# bluetooth.net
KiCad netlist of a schematic drawn in EAGLE
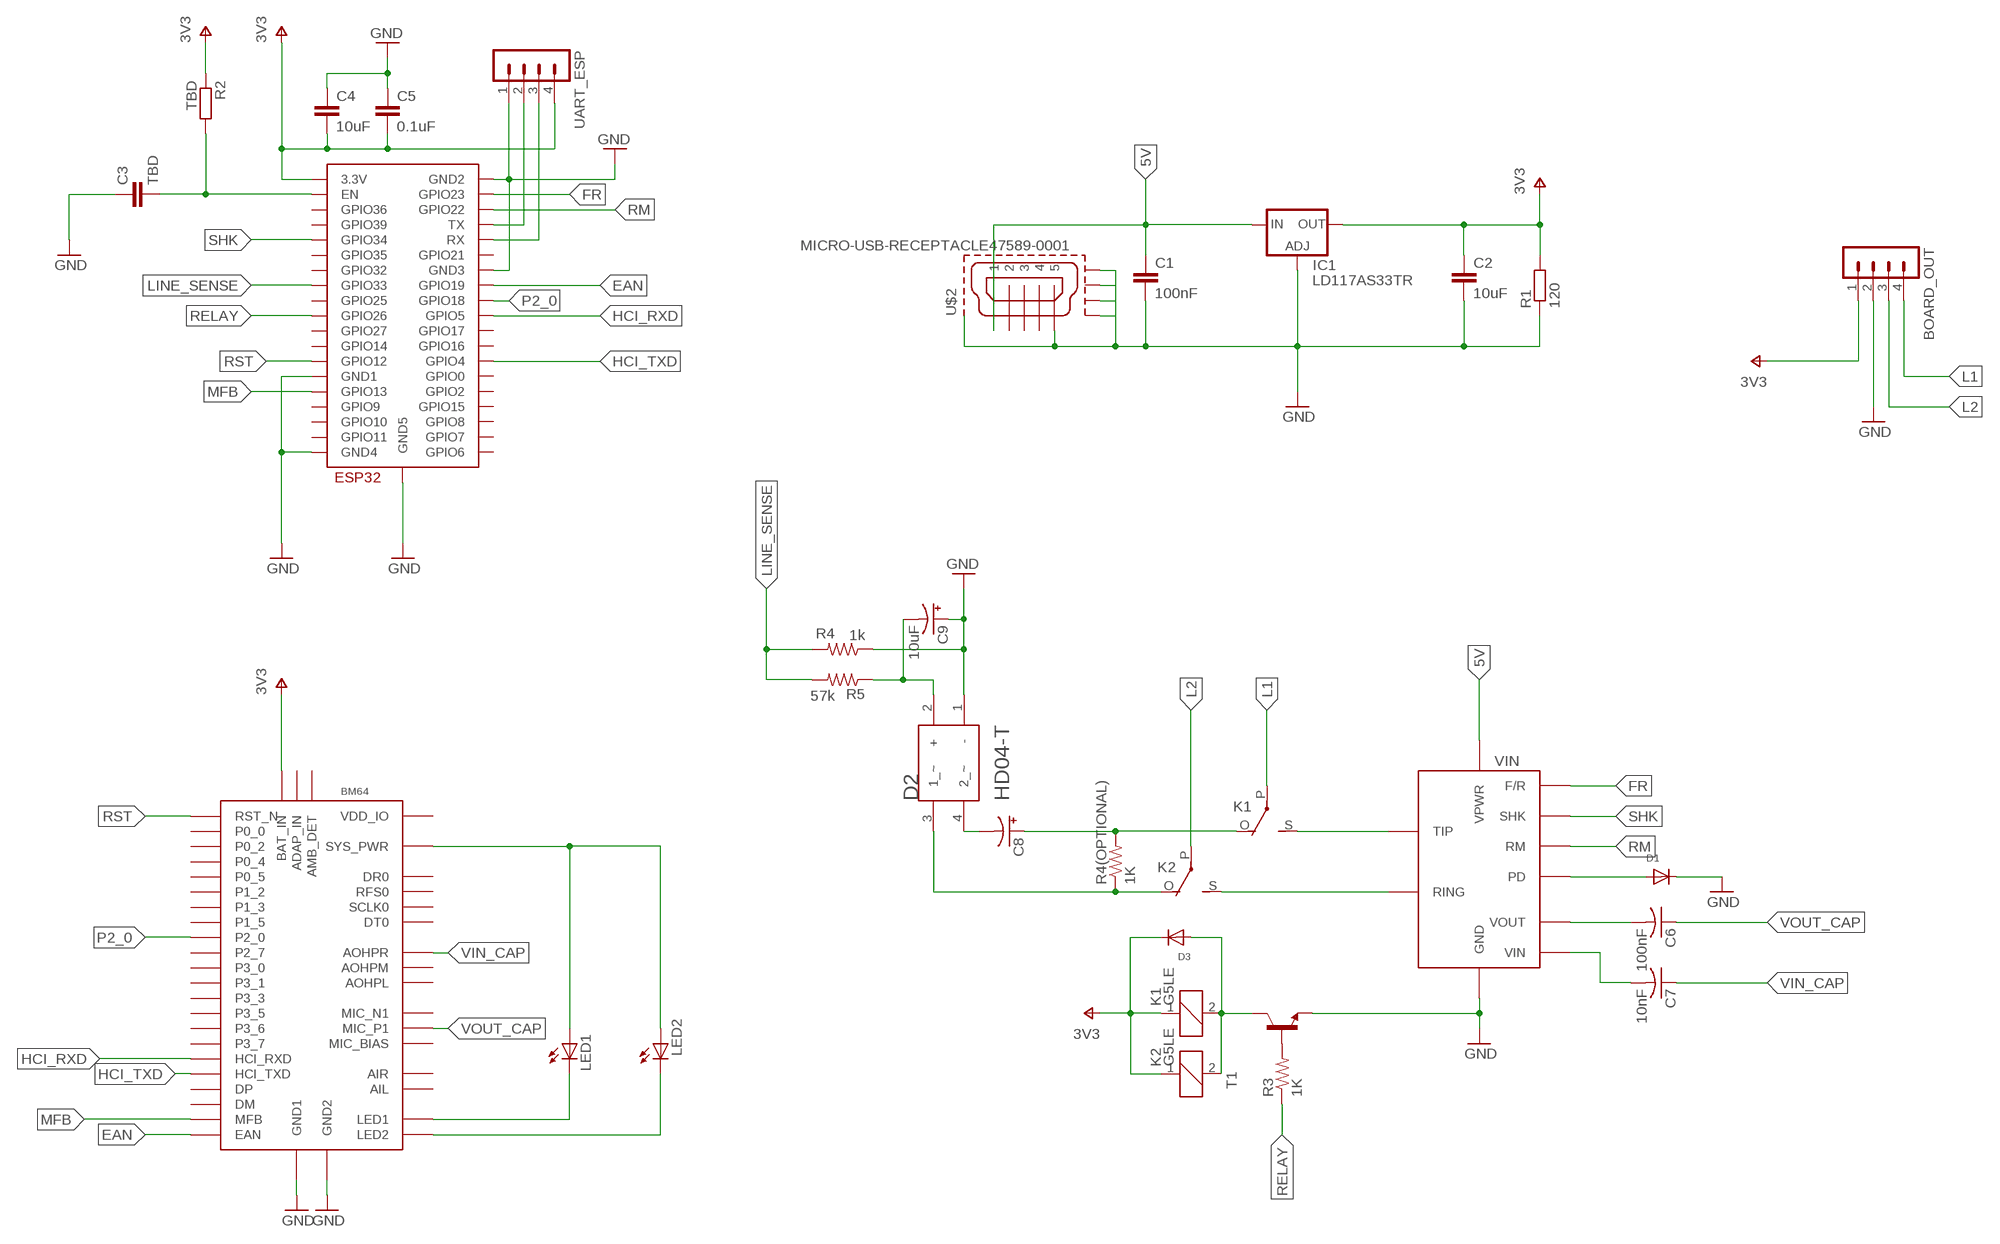
[diagram p0: schematic, sheet 1]

(export (version "E")
  (design (tool "Eeschema 10.0.6"))
  (components
    (comp (ref "BM64")
      (value "DJD_EAGLE_LIBRARY_BM64")
      (footprint "eagle-import:DJD_EAGLE_LIBRARY_BM64")
      (libsource (lib "eagle-import") (part "DJD_EAGLE_LIBRARY_BM64"))
    )
    (comp (ref "BOARD_OUT")
      (value "MA04-1")
      (footprint "eagle-import:MA04-1")
      (libsource (lib "eagle-import") (part "MA04-1"))
    )
    (comp (ref "C1")
      (value "100nF")
      (footprint "eagle-import:C0805")
      (libsource (lib "eagle-import") (part "C-EUC0805"))
    )
    (comp (ref "C2")
      (value "10uF")
      (footprint "eagle-import:C0805")
      (libsource (lib "eagle-import") (part "C-EUC0805"))
    )
    (comp (ref "C3")
      (value "TBD")
      (footprint "eagle-import:C0805")
      (libsource (lib "eagle-import") (part "C-EUC0805"))
    )
    (comp (ref "C4")
      (value "10uF")
      (footprint "eagle-import:C0805")
      (libsource (lib "eagle-import") (part "C-EUC0805"))
    )
    (comp (ref "C5")
      (value "0.1uF")
      (footprint "eagle-import:C0805")
      (libsource (lib "eagle-import") (part "C-EUC0805"))
    )
    (comp (ref "C6")
      (value "100nF")
      (footprint "eagle-import:C0805")
      (libsource (lib "eagle-import") (part "C-USC0805"))
    )
    (comp (ref "C7")
      (value "10nF")
      (footprint "eagle-import:C0805")
      (libsource (lib "eagle-import") (part "C-USC0805"))
    )
    (comp (ref "C8")
      (value "CPOL-USE2-5")
      (footprint "eagle-import:E2-5")
      (libsource (lib "eagle-import") (part "CPOL-USE2-5"))
    )
    (comp (ref "C9")
      (value "10uF")
      (footprint "eagle-import:CPOL-RADIAL-2.5MM-5MM")
      (libsource (lib "eagle-import") (part "10UF-POLAR-RADIAL-2.5MM-25V-20%"))
    )
    (comp (ref "D1")
      (value "DIODESMA")
      (footprint "eagle-import:SMADIODE")
      (libsource (lib "eagle-import") (part "DIODESMA"))
    )
    (comp (ref "D2")
      (value "DIODES_HD04-TDIODES_HD04-T_0_0")
      (footprint "eagle-import:DIODES_HD04-T_0")
      (fields
        (field (name "DIGIKEY_PART_NUMBER") "HD04DICT-ND")
        (field (name "MF") "Diodes")
        (field (name "MOUSER_PART_NUMBER") "621-HD04T")
      )
      (libsource (lib "eagle-import") (part "DIODES_HD04-TDIODES_HD04-T_0_0"))
    )
    (comp (ref "D3")
      (value "DIODESOD-123")
      (footprint "eagle-import:SOD-123")
      (libsource (lib "eagle-import") (part "DIODESOD-123"))
    )
    (comp (ref "IC1")
      (value "LD117AS33TR")
      (footprint "eagle-import:SOT223")
      (libsource (lib "eagle-import") (part "LD117A?S33TR"))
    )
    (comp (ref "K1")
      (value "G5LE")
      (footprint "eagle-import:G5LE")
      (libsource (lib "eagle-import") (part "G5LE"))
    )
    (comp (ref "K2")
      (value "G5LE")
      (footprint "eagle-import:G5LE")
      (libsource (lib "eagle-import") (part "G5LE"))
    )
    (comp (ref "LED1")
      (value "LEDCHIP-LED0805")
      (footprint "eagle-import:CHIP-LED0805")
      (libsource (lib "eagle-import") (part "LEDCHIP-LED0805"))
    )
    (comp (ref "LED2")
      (value "LEDCHIP-LED0805")
      (footprint "eagle-import:CHIP-LED0805")
      (libsource (lib "eagle-import") (part "LEDCHIP-LED0805"))
    )
    (comp (ref "R1")
      (value "120")
      (footprint "eagle-import:M0805")
      (libsource (lib "eagle-import") (part "R-EU_M0805"))
    )
    (comp (ref "R2")
      (value "TBD")
      (footprint "eagle-import:M0805")
      (libsource (lib "eagle-import") (part "R-EU_M0805"))
    )
    (comp (ref "R3")
      (value "1K")
      (footprint "eagle-import:M0805")
      (libsource (lib "eagle-import") (part "R-US_M0805"))
    )
    (comp (ref "R4")
      (value "1k")
      (footprint "eagle-import:M0805")
      (libsource (lib "eagle-import") (part "R-US_M0805"))
    )
    (comp (ref "R4(OPTIONAL)")
      (value "1K")
      (footprint "eagle-import:M0805")
      (libsource (lib "eagle-import") (part "R-US_M0805"))
    )
    (comp (ref "R5")
      (value "57k")
      (footprint "eagle-import:M0805")
      (libsource (lib "eagle-import") (part "R-US_M0805"))
    )
    (comp (ref "T1")
      (value "-NPN-SOT23-EBC")
      (footprint "eagle-import:SOT23-EBC")
      (libsource (lib "eagle-import") (part "-NPN-SOT23-EBC"))
    )
    (comp (ref "U$1")
      (value "ESP32-WROOM")
      (footprint "eagle-import:ESP32-WROOM")
      (libsource (lib "eagle-import") (part "ESP32-WROOM"))
    )
    (comp (ref "U$2")
      (value "MICRO-USB-RECEPTACLE47589-0001")
      (footprint "eagle-import:47589-0001")
      (libsource (lib "eagle-import") (part "MICRO-USB-RECEPTACLE47589-0001"))
    )
    (comp (ref "UART_ESP")
      (value "MA04-1")
      (footprint "eagle-import:MA04-1")
      (libsource (lib "eagle-import") (part "MA04-1"))
    )
    (comp (ref "VIN")
      (value "DJD_EAGLE_LIBRARY_AG1171SIL")
      (footprint "eagle-import:DJD_EAGLE_LIBRARY_AG1171")
      (libsource (lib "eagle-import") (part "DJD_EAGLE_LIBRARY_AG1171SIL"))
    )
  )
  (nets
    (net (code "1") (name "/ADAP_IN") (class "Default")
      (node (ref "BM64") (pin "23") (pinfunction "ADAP_IN_23") (pintype "power_in"))
    )
    (net (code "2") (name "/MIC_BIAS") (class "Default")
      (node (ref "BM64") (pin "10") (pinfunction "MIC_BIAS_10") (pintype "power_in"))
    )
    (net (code "3") (name "/VDD_IO") (class "Default")
      (node (ref "BM64") (pin "21") (pinfunction "VDD_IO_21") (pintype "power_in"))
    )
    (net (code "4") (name "3V3") (class "Default")
      (node (ref "BM64") (pin "22") (pinfunction "BAT_IN_22") (pintype "power_in"))
      (node (ref "BOARD_OUT") (pin "1") (pinfunction "1_1") (pintype "passive"))
      (node (ref "C2") (pin "1") (pinfunction "1_1") (pintype "passive"))
      (node (ref "C4") (pin "2") (pinfunction "2_2") (pintype "passive"))
      (node (ref "C5") (pin "2") (pinfunction "2_2") (pintype "passive"))
      (node (ref "D3") (pin "C") (pinfunction "C_C") (pintype "passive"))
      (node (ref "IC1") (pin "4") (pinfunction "OUT_4") (pintype "passive"))
      (node (ref "K1") (pin "1") (pinfunction "1_1") (pintype "passive"))
      (node (ref "K2") (pin "1") (pinfunction "1_1") (pintype "passive"))
      (node (ref "R1") (pin "2") (pinfunction "2_2") (pintype "passive"))
      (node (ref "R2") (pin "1") (pinfunction "1_1") (pintype "passive"))
      (node (ref "U$1") (pin "3V3") (pinfunction "3.3V_3V3") (pintype "bidirectional"))
      (node (ref "UART_ESP") (pin "4") (pinfunction "4_4") (pintype "passive"))
    )
    (net (code "5") (name "5V") (class "Default")
      (node (ref "C1") (pin "1") (pinfunction "1_1") (pintype "passive"))
      (node (ref "IC1") (pin "3") (pinfunction "IN_3") (pintype "input"))
      (node (ref "U$2") (pin "1") (pinfunction "1_1") (pintype "input"))
      (node (ref "VIN") (pin "P$13") (pinfunction "VPWR_P$13") (pintype "power_in"))
    )
    (net (code "6") (name "EAN") (class "Default")
      (node (ref "BM64") (pin "32") (pinfunction "EAN_32") (pintype "input"))
      (node (ref "U$1") (pin "IO19") (pinfunction "GPIO19_IO19") (pintype "bidirectional"))
    )
    (net (code "7") (name "FR") (class "Default")
      (node (ref "U$1") (pin "IO23") (pinfunction "GPIO23_IO23") (pintype "bidirectional"))
      (node (ref "VIN") (pin "P$3") (pinfunction "F/R_P$3") (pintype "input"))
    )
    (net (code "8") (name "GND") (class "Default")
      (node (ref "BM64") (pin "14") (pinfunction "GND1_14") (pintype "power_in"))
      (node (ref "BM64") (pin "43") (pinfunction "GND2_43") (pintype "power_in"))
      (node (ref "BOARD_OUT") (pin "2") (pinfunction "2_2") (pintype "passive"))
      (node (ref "C1") (pin "2") (pinfunction "2_2") (pintype "passive"))
      (node (ref "C2") (pin "2") (pinfunction "2_2") (pintype "passive"))
      (node (ref "C3") (pin "1") (pinfunction "1_1") (pintype "passive"))
      (node (ref "C4") (pin "1") (pinfunction "1_1") (pintype "passive"))
      (node (ref "C5") (pin "1") (pinfunction "1_1") (pintype "passive"))
      (node (ref "C9") (pin "1") (pinfunction "+_1") (pintype "passive"))
      (node (ref "D1") (pin "C") (pinfunction "C_C") (pintype "passive"))
      (node (ref "D2") (pin "1") (pinfunction "-_1") (pintype "passive"))
      (node (ref "IC1") (pin "1") (pinfunction "ADJ_1") (pintype "input"))
      (node (ref "R1") (pin "1") (pinfunction "1_1") (pintype "passive"))
      (node (ref "R4") (pin "1") (pinfunction "1_1") (pintype "passive"))
      (node (ref "T1") (pin "E") (pinfunction "E_E") (pintype "passive"))
      (node (ref "U$1") (pin "GND1") (pinfunction "GND1_GND1") (pintype "bidirectional"))
      (node (ref "U$1") (pin "GND2") (pinfunction "GND2_GND2") (pintype "bidirectional"))
      (node (ref "U$1") (pin "GND3") (pinfunction "GND3_GND3") (pintype "bidirectional"))
      (node (ref "U$1") (pin "GND4") (pinfunction "GND4_GND4") (pintype "bidirectional"))
      (node (ref "U$1") (pin "GND5") (pinfunction "GND5_GND5") (pintype "bidirectional"))
      (node (ref "U$2") (pin "5") (pinfunction "5_5") (pintype "input"))
      (node (ref "U$2") (pin "CASING1") (pinfunction "GND1_CASING1") (pintype "bidirectional"))
      (node (ref "U$2") (pin "CASING2") (pinfunction "GND2_CASING2") (pintype "bidirectional"))
      (node (ref "U$2") (pin "CASING3") (pinfunction "GND3_CASING3") (pintype "bidirectional"))
      (node (ref "U$2") (pin "CASING4") (pinfunction "GND4_CASING4") (pintype "bidirectional"))
      (node (ref "UART_ESP") (pin "1") (pinfunction "1_1") (pintype "passive"))
      (node (ref "VIN") (pin "P$12") (pinfunction "GND_P$12") (pintype "power_in"))
    )
    (net (code "9") (name "HCI_RXD") (class "Default")
      (node (ref "BM64") (pin "19") (pinfunction "HCI_RXD_19") (pintype "input"))
      (node (ref "U$1") (pin "IO5") (pinfunction "GPIO5_IO5") (pintype "bidirectional"))
    )
    (net (code "10") (name "HCI_TXD") (class "Default")
      (node (ref "BM64") (pin "20") (pinfunction "HCI_TXD_20") (pintype "output"))
      (node (ref "U$1") (pin "IO4") (pinfunction "GPIO4_IO4") (pintype "bidirectional"))
    )
    (net (code "11") (name "L1") (class "Default")
      (node (ref "BOARD_OUT") (pin "4") (pinfunction "4_4") (pintype "passive"))
      (node (ref "K1") (pin "P") (pinfunction "P_P") (pintype "passive"))
    )
    (net (code "12") (name "L2") (class "Default")
      (node (ref "BOARD_OUT") (pin "3") (pinfunction "3_3") (pintype "passive"))
      (node (ref "K2") (pin "P") (pinfunction "P_P") (pintype "passive"))
    )
    (net (code "13") (name "LINE_SENSE") (class "Default")
      (node (ref "R4") (pin "2") (pinfunction "2_2") (pintype "passive"))
      (node (ref "R5") (pin "2") (pinfunction "2_2") (pintype "passive"))
      (node (ref "U$1") (pin "IO33") (pinfunction "GPIO33_IO33") (pintype "bidirectional"))
    )
    (net (code "14") (name "MFB") (class "Default")
      (node (ref "BM64") (pin "26") (pinfunction "MFB_26") (pintype "input"))
      (node (ref "U$1") (pin "IO13") (pinfunction "GPIO13_IO13") (pintype "bidirectional"))
    )
    (net (code "15") (name "Net-(BM64-LED1)") (class "Default")
      (node (ref "BM64") (pin "28") (pinfunction "LED1_28") (pintype "output"))
      (node (ref "LED1") (pin "C") (pinfunction "C_C") (pintype "passive"))
    )
    (net (code "16") (name "Net-(BM64-LED2)") (class "Default")
      (node (ref "BM64") (pin "27") (pinfunction "LED2_27") (pintype "output"))
      (node (ref "LED2") (pin "C") (pinfunction "C_C") (pintype "passive"))
    )
    (net (code "17") (name "Net-(BM64-SYS_PWR)") (class "Default")
      (node (ref "BM64") (pin "24") (pinfunction "SYS_PWR_24") (pintype "power_in"))
      (node (ref "LED1") (pin "A") (pinfunction "A_A") (pintype "passive"))
      (node (ref "LED2") (pin "A") (pinfunction "A_A") (pintype "passive"))
    )
    (net (code "18") (name "Net-(C3-Pad2)") (class "Default")
      (node (ref "C3") (pin "2") (pinfunction "2_2") (pintype "passive"))
      (node (ref "R2") (pin "2") (pinfunction "2_2") (pintype "passive"))
      (node (ref "U$1") (pin "EN") (pinfunction "EN_EN") (pintype "bidirectional"))
    )
    (net (code "19") (name "Net-(C8-Pad+)") (class "Default")
      (node (ref "C8") (pin "+") (pinfunction "+_+") (pintype "passive"))
      (node (ref "K1") (pin "O") (pinfunction "O_O") (pintype "passive"))
      (node (ref "R4(OPTIONAL)") (pin "2") (pinfunction "2_2") (pintype "passive"))
    )
    (net (code "20") (name "Net-(C9--)") (class "Default")
      (node (ref "C9") (pin "2") (pinfunction "-_2") (pintype "passive"))
      (node (ref "D2") (pin "2") (pinfunction "+_2") (pintype "passive"))
      (node (ref "R5") (pin "1") (pinfunction "1_1") (pintype "passive"))
    )
    (net (code "21") (name "Net-(D2-1_~{})") (class "Default")
      (node (ref "D2") (pin "3") (pinfunction "1_~{}_3") (pintype "passive"))
      (node (ref "K2") (pin "O") (pinfunction "O_O") (pintype "passive"))
      (node (ref "R4(OPTIONAL)") (pin "1") (pinfunction "1_1") (pintype "passive"))
    )
    (net (code "22") (name "Net-(D2-2_~{})") (class "Default")
      (node (ref "C8") (pin "-") (pinfunction "-_-") (pintype "passive"))
      (node (ref "D2") (pin "4") (pinfunction "2_~{}_4") (pintype "passive"))
    )
    (net (code "23") (name "Net-(D3-PadA)") (class "Default")
      (node (ref "D3") (pin "A") (pinfunction "A_A") (pintype "passive"))
      (node (ref "K1") (pin "2") (pinfunction "2_2") (pintype "passive"))
      (node (ref "K2") (pin "2") (pinfunction "2_2") (pintype "passive"))
      (node (ref "T1") (pin "C") (pinfunction "C_C") (pintype "passive"))
    )
    (net (code "24") (name "Net-(R3-Pad2)") (class "Default")
      (node (ref "R3") (pin "2") (pinfunction "2_2") (pintype "passive"))
      (node (ref "T1") (pin "B") (pinfunction "B_B") (pintype "passive"))
    )
    (net (code "25") (name "Net-(U$1-PadRX)") (class "Default")
      (node (ref "U$1") (pin "RX") (pinfunction "RX_RX") (pintype "bidirectional"))
      (node (ref "UART_ESP") (pin "3") (pinfunction "3_3") (pintype "passive"))
    )
    (net (code "26") (name "Net-(U$1-PadTX)") (class "Default")
      (node (ref "U$1") (pin "TX") (pinfunction "TX_TX") (pintype "bidirectional"))
      (node (ref "UART_ESP") (pin "2") (pinfunction "2_2") (pintype "passive"))
    )
    (net (code "27") (name "Net-(VIN-PD)") (class "Default")
      (node (ref "D1") (pin "A") (pinfunction "A_A") (pintype "passive"))
      (node (ref "VIN") (pin "P$14") (pinfunction "PD_P$14") (pintype "input"))
    )
    (net (code "28") (name "Net-(VIN-RING)") (class "Default")
      (node (ref "K2") (pin "S") (pinfunction "S_S") (pintype "passive"))
      (node (ref "VIN") (pin "P$1") (pinfunction "RING_P$1") (pintype "bidirectional"))
    )
    (net (code "29") (name "Net-(VIN-TIP)") (class "Default")
      (node (ref "K1") (pin "S") (pinfunction "S_S") (pintype "passive"))
      (node (ref "VIN") (pin "P$2") (pinfunction "TIP_P$2") (pintype "bidirectional"))
    )
    (net (code "30") (name "Net-(VIN-VIN)") (class "Default")
      (node (ref "C7") (pin "2") (pinfunction "2_2") (pintype "passive"))
      (node (ref "VIN") (pin "P$9") (pinfunction "VIN_P$9") (pintype "input"))
    )
    (net (code "31") (name "Net-(VIN-VOUT)") (class "Default")
      (node (ref "C6") (pin "2") (pinfunction "2_2") (pintype "passive"))
      (node (ref "VIN") (pin "P$10") (pinfunction "VOUT_P$10") (pintype "output"))
    )
    (net (code "32") (name "P2_0") (class "Default")
      (node (ref "BM64") (pin "41") (pinfunction "P2_0_41") (pintype "bidirectional"))
      (node (ref "U$1") (pin "IO18") (pinfunction "GPIO18_IO18") (pintype "bidirectional"))
    )
    (net (code "33") (name "RELAY") (class "Default")
      (node (ref "R3") (pin "1") (pinfunction "1_1") (pintype "passive"))
      (node (ref "U$1") (pin "IO26") (pinfunction "GPIO26_IO26") (pintype "bidirectional"))
    )
    (net (code "34") (name "RM") (class "Default")
      (node (ref "U$1") (pin "IO22") (pinfunction "GPIO22_IO22") (pintype "bidirectional"))
      (node (ref "VIN") (pin "P$4") (pinfunction "RM_P$4") (pintype "input"))
    )
    (net (code "35") (name "RST") (class "Default")
      (node (ref "BM64") (pin "13") (pinfunction "RST_N_13") (pintype "input"))
      (node (ref "U$1") (pin "IO12") (pinfunction "GPIO12_IO12") (pintype "bidirectional"))
    )
    (net (code "36") (name "SHK") (class "Default")
      (node (ref "U$1") (pin "IO34") (pinfunction "GPIO34_IO34") (pintype "bidirectional"))
      (node (ref "VIN") (pin "P$5") (pinfunction "SHK_P$5") (pintype "output"))
    )
    (net (code "37") (name "VIN_CAP") (class "Default")
      (node (ref "BM64") (pin "5") (pinfunction "AOHPR_5") (pintype "passive"))
      (node (ref "C7") (pin "1") (pinfunction "1_1") (pintype "passive"))
    )
    (net (code "38") (name "VOUT_CAP") (class "Default")
      (node (ref "BM64") (pin "9") (pinfunction "MIC_P1_9") (pintype "passive"))
      (node (ref "C6") (pin "1") (pinfunction "1_1") (pintype "passive"))
    )
    (net (code "39") (name "unconnected-(BM64-AIL-Pad12)") (class "Default")
      (node (ref "BM64") (pin "12") (pinfunction "AIL_12") (pintype "passive"))
    )
    (net (code "40") (name "unconnected-(BM64-AIR-Pad11)") (class "Default")
      (node (ref "BM64") (pin "11") (pinfunction "AIR_11") (pintype "passive"))
    )
    (net (code "41") (name "unconnected-(BM64-AMB_DET-Pad25)") (class "Default")
      (node (ref "BM64") (pin "25") (pinfunction "AMB_DET_25") (pintype "passive"))
    )
    (net (code "42") (name "unconnected-(BM64-AOHPL-Pad7)") (class "Default")
      (node (ref "BM64") (pin "7") (pinfunction "AOHPL_7") (pintype "passive"))
    )
    (net (code "43") (name "unconnected-(BM64-AOHPM-Pad6)") (class "Default")
      (node (ref "BM64") (pin "6") (pinfunction "AOHPM_6") (pintype "passive"))
    )
    (net (code "44") (name "unconnected-(BM64-DM-Pad33)") (class "Default")
      (node (ref "BM64") (pin "33") (pinfunction "DM_33") (pintype "bidirectional"))
    )
    (net (code "45") (name "unconnected-(BM64-DP-Pad34)") (class "Default")
      (node (ref "BM64") (pin "34") (pinfunction "DP_34") (pintype "bidirectional"))
    )
    (net (code "46") (name "unconnected-(BM64-DR0-Pad1)") (class "Default")
      (node (ref "BM64") (pin "1") (pinfunction "DR0_1") (pintype "bidirectional"))
    )
    (net (code "47") (name "unconnected-(BM64-DT0-Pad4)") (class "Default")
      (node (ref "BM64") (pin "4") (pinfunction "DT0_4") (pintype "bidirectional"))
    )
    (net (code "48") (name "unconnected-(BM64-MIC_N1-Pad8)") (class "Default")
      (node (ref "BM64") (pin "8") (pinfunction "MIC_N1_8") (pintype "passive"))
    )
    (net (code "49") (name "unconnected-(BM64-P0_0-Pad31)") (class "Default")
      (node (ref "BM64") (pin "31") (pinfunction "P0_0_31") (pintype "bidirectional"))
    )
    (net (code "50") (name "unconnected-(BM64-P0_2-Pad40)") (class "Default")
      (node (ref "BM64") (pin "40") (pinfunction "P0_2_40") (pintype "bidirectional"))
    )
    (net (code "51") (name "unconnected-(BM64-P0_4-Pad17)") (class "Default")
      (node (ref "BM64") (pin "17") (pinfunction "P0_4_17") (pintype "bidirectional"))
    )
    (net (code "52") (name "unconnected-(BM64-P0_5-Pad35)") (class "Default")
      (node (ref "BM64") (pin "35") (pinfunction "P0_5_35") (pintype "bidirectional"))
    )
    (net (code "53") (name "unconnected-(BM64-P1_2-Pad15)") (class "Default")
      (node (ref "BM64") (pin "15") (pinfunction "P1_2_15") (pintype "bidirectional"))
    )
    (net (code "54") (name "unconnected-(BM64-P1_3-Pad16)") (class "Default")
      (node (ref "BM64") (pin "16") (pinfunction "P1_3_16") (pintype "bidirectional"))
    )
    (net (code "55") (name "unconnected-(BM64-P1_5-Pad18)") (class "Default")
      (node (ref "BM64") (pin "18") (pinfunction "P1_5_18") (pintype "bidirectional"))
    )
    (net (code "56") (name "unconnected-(BM64-P2_7-Pad42)") (class "Default")
      (node (ref "BM64") (pin "42") (pinfunction "P2_7_42") (pintype "bidirectional"))
    )
    (net (code "57") (name "unconnected-(BM64-P3_0-Pad36)") (class "Default")
      (node (ref "BM64") (pin "36") (pinfunction "P3_0_36") (pintype "bidirectional"))
    )
    (net (code "58") (name "unconnected-(BM64-P3_1-Pad37)") (class "Default")
      (node (ref "BM64") (pin "37") (pinfunction "P3_1_37") (pintype "bidirectional"))
    )
    (net (code "59") (name "unconnected-(BM64-P3_3-Pad38)") (class "Default")
      (node (ref "BM64") (pin "38") (pinfunction "P3_3_38") (pintype "bidirectional"))
    )
    (net (code "60") (name "unconnected-(BM64-P3_5-Pad30)") (class "Default")
      (node (ref "BM64") (pin "30") (pinfunction "P3_5_30") (pintype "bidirectional"))
    )
    (net (code "61") (name "unconnected-(BM64-P3_6-Pad39)") (class "Default")
      (node (ref "BM64") (pin "39") (pinfunction "P3_6_39") (pintype "bidirectional"))
    )
    (net (code "62") (name "unconnected-(BM64-P3_7-Pad29)") (class "Default")
      (node (ref "BM64") (pin "29") (pinfunction "P3_7_29") (pintype "bidirectional"))
    )
    (net (code "63") (name "unconnected-(BM64-RFS0-Pad2)") (class "Default")
      (node (ref "BM64") (pin "2") (pinfunction "RFS0_2") (pintype "bidirectional"))
    )
    (net (code "64") (name "unconnected-(BM64-SCLK0-Pad3)") (class "Default")
      (node (ref "BM64") (pin "3") (pinfunction "SCLK0_3") (pintype "bidirectional"))
    )
    (net (code "65") (name "unconnected-(U$1-GPIO0-PadIO0)") (class "Default")
      (node (ref "U$1") (pin "IO0") (pinfunction "GPIO0_IO0") (pintype "bidirectional"))
    )
    (net (code "66") (name "unconnected-(U$1-GPIO2-PadIO2)") (class "Default")
      (node (ref "U$1") (pin "IO2") (pinfunction "GPIO2_IO2") (pintype "bidirectional"))
    )
    (net (code "67") (name "unconnected-(U$1-GPIO6-PadCLK)") (class "Default")
      (node (ref "U$1") (pin "CLK") (pinfunction "GPIO6_CLK") (pintype "bidirectional"))
    )
    (net (code "68") (name "unconnected-(U$1-GPIO7-PadSD0)") (class "Default")
      (node (ref "U$1") (pin "SD0") (pinfunction "GPIO7_SD0") (pintype "bidirectional"))
    )
    (net (code "69") (name "unconnected-(U$1-GPIO8-PadSD1)") (class "Default")
      (node (ref "U$1") (pin "SD1") (pinfunction "GPIO8_SD1") (pintype "bidirectional"))
    )
    (net (code "70") (name "unconnected-(U$1-GPIO9-PadSD2)") (class "Default")
      (node (ref "U$1") (pin "SD2") (pinfunction "GPIO9_SD2") (pintype "bidirectional"))
    )
    (net (code "71") (name "unconnected-(U$1-GPIO10-PadSD3)") (class "Default")
      (node (ref "U$1") (pin "SD3") (pinfunction "GPIO10_SD3") (pintype "bidirectional"))
    )
    (net (code "72") (name "unconnected-(U$1-GPIO11-PadCMD)") (class "Default")
      (node (ref "U$1") (pin "CMD") (pinfunction "GPIO11_CMD") (pintype "bidirectional"))
    )
    (net (code "73") (name "unconnected-(U$1-GPIO14-PadIO14)") (class "Default")
      (node (ref "U$1") (pin "IO14") (pinfunction "GPIO14_IO14") (pintype "bidirectional"))
    )
    (net (code "74") (name "unconnected-(U$1-GPIO15-PadIO15)") (class "Default")
      (node (ref "U$1") (pin "IO15") (pinfunction "GPIO15_IO15") (pintype "bidirectional"))
    )
    (net (code "75") (name "unconnected-(U$1-GPIO16-PadIO16)") (class "Default")
      (node (ref "U$1") (pin "IO16") (pinfunction "GPIO16_IO16") (pintype "bidirectional"))
    )
    (net (code "76") (name "unconnected-(U$1-GPIO17-PadIO17)") (class "Default")
      (node (ref "U$1") (pin "IO17") (pinfunction "GPIO17_IO17") (pintype "bidirectional"))
    )
    (net (code "77") (name "unconnected-(U$1-GPIO21-PadIO21)") (class "Default")
      (node (ref "U$1") (pin "IO21") (pinfunction "GPIO21_IO21") (pintype "bidirectional"))
    )
    (net (code "78") (name "unconnected-(U$1-GPIO25-PadIO25)") (class "Default")
      (node (ref "U$1") (pin "IO25") (pinfunction "GPIO25_IO25") (pintype "bidirectional"))
    )
    (net (code "79") (name "unconnected-(U$1-GPIO27-PadIO27)") (class "Default")
      (node (ref "U$1") (pin "IO27") (pinfunction "GPIO27_IO27") (pintype "bidirectional"))
    )
    (net (code "80") (name "unconnected-(U$1-GPIO32-PadIO32)") (class "Default")
      (node (ref "U$1") (pin "IO32") (pinfunction "GPIO32_IO32") (pintype "bidirectional"))
    )
    (net (code "81") (name "unconnected-(U$1-GPIO35-PadIO35)") (class "Default")
      (node (ref "U$1") (pin "IO35") (pinfunction "GPIO35_IO35") (pintype "bidirectional"))
    )
    (net (code "82") (name "unconnected-(U$1-GPIO36-PadSENSOR_VP)") (class "Default")
      (node (ref "U$1") (pin "SENSOR_VP") (pinfunction "GPIO36_SENSOR_VP") (pintype "bidirectional"))
    )
    (net (code "83") (name "unconnected-(U$1-GPIO39-PadSENSOR_VN)") (class "Default")
      (node (ref "U$1") (pin "SENSOR_VN") (pinfunction "GPIO39_SENSOR_VN") (pintype "bidirectional"))
    )
    (net (code "84") (name "unconnected-(U$2-Pad2)") (class "Default")
      (node (ref "U$2") (pin "2") (pinfunction "2_2") (pintype "input"))
    )
    (net (code "85") (name "unconnected-(U$2-Pad3)") (class "Default")
      (node (ref "U$2") (pin "3") (pinfunction "3_3") (pintype "input"))
    )
    (net (code "86") (name "unconnected-(U$2-Pad4)") (class "Default")
      (node (ref "U$2") (pin "4") (pinfunction "4_4") (pintype "input"))
    )
  )
)
